# Sheet1.net
KiCad netlist of a schematic drawn in Altium Designer
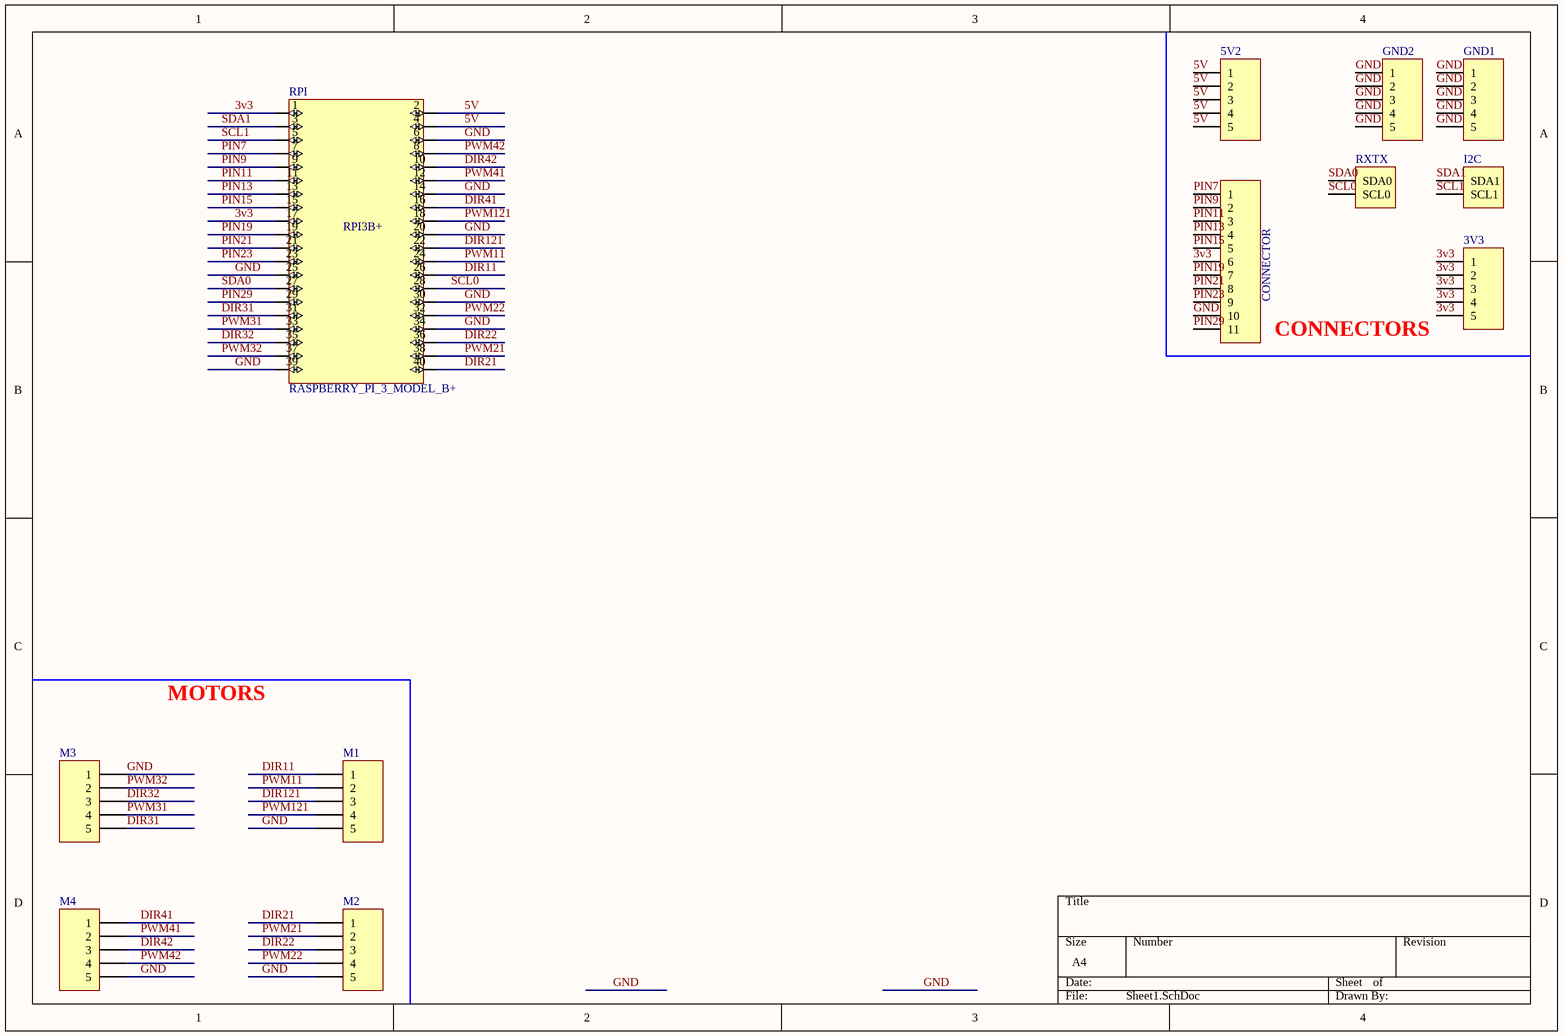
[diagram p0: Sheet1.SchDoc]

(export (version "E")
  (design (tool "Eeschema 10.0.6"))
  (components
    (comp (ref "3V3")
      (value "Header 5")
      (footprint "HDR1X5")
      (description "Header, 5-Pin")
      (fields (field (name "PUBLISHER") "Altium Limited"))
      (libsource (lib "Miscellaneous Connectors") (part "Header 5"))
    )
    (comp (ref "5V2")
      (value "Header 5")
      (footprint "HDR1X5")
      (description "Header, 5-Pin")
      (fields (field (name "PUBLISHER") "Altium Limited"))
      (libsource (lib "Miscellaneous Connectors") (part "Header 5"))
    )
    (comp (ref "CONNECTOR")
      (value "Header 11")
      (footprint "HDR1X11")
      (description "Header, 11-Pin")
      (fields (field (name "PUBLISHER") "Altium Limited"))
      (libsource (lib "Miscellaneous Connectors") (part "Header 11"))
    )
    (comp (ref "GND1")
      (value "Header 5")
      (footprint "HDR1X5")
      (description "Header, 5-Pin")
      (fields (field (name "PUBLISHER") "Altium Limited"))
      (libsource (lib "Miscellaneous Connectors") (part "Header 5"))
    )
    (comp (ref "GND2")
      (value "Header 5")
      (footprint "HDR1X5")
      (description "Header, 5-Pin")
      (fields (field (name "PUBLISHER") "Altium Limited"))
      (libsource (lib "Miscellaneous Connectors") (part "Header 5"))
    )
    (comp (ref "I2C")
      (value "Header 2")
      (footprint "HDR1X2")
      (description "Header, 2-Pin")
      (fields (field (name "PUBLISHER") "Altium Limited"))
      (libsource (lib "Miscellaneous Connectors") (part "Header 2"))
    )
    (comp (ref "M1")
      (value "Header 5")
      (footprint "HDR1X5")
      (description "Header, 5-Pin")
      (fields (field (name "PUBLISHER") "Altium Limited"))
      (libsource (lib "Miscellaneous Connectors") (part "Header 5"))
    )
    (comp (ref "M2")
      (value "Header 5")
      (footprint "HDR1X5")
      (description "Header, 5-Pin")
      (fields (field (name "PUBLISHER") "Altium Limited"))
      (libsource (lib "Miscellaneous Connectors") (part "Header 5"))
    )
    (comp (ref "M3")
      (value "Header 5")
      (footprint "HDR1X5")
      (description "Header, 5-Pin")
      (fields (field (name "PUBLISHER") "Altium Limited"))
      (libsource (lib "") (part "Header 5_1"))
    )
    (comp (ref "M4")
      (value "Header 5")
      (footprint "HDR1X5")
      (description "Header, 5-Pin")
      (fields (field (name "PUBLISHER") "Altium Limited"))
      (libsource (lib "") (part "Header 5_1"))
    )
    (comp (ref "RPI")
      (value "RASPBERRY_PI_3_MODEL_B+")
      (footprint "MODULE_RASPBERRY_PI_3_MODEL_B+")
      (fields (field (name "MF") "Raspberry Pi") (field (name "MP") "RASPBERRY PI 3 MODEL B+"))
      (libsource (lib "RASPBERRY_PI_3_MODEL_B+") (part "RASPBERRY_PI_3_MODEL_B+"))
    )
    (comp (ref "RXTX")
      (value "Header 2")
      (footprint "HDR1X2")
      (description "Header, 2-Pin")
      (fields (field (name "PUBLISHER") "Altium Limited"))
      (libsource (lib "Miscellaneous Connectors") (part "Header 2"))
    )
  )
  (nets
    (net (code "1") (name "/3v3") (class "Default")
      (node (ref "3V3") (pin "1") (pinfunction "1_1") (pintype "passive"))
      (node (ref "3V3") (pin "2") (pinfunction "2_2") (pintype "passive"))
      (node (ref "3V3") (pin "3") (pinfunction "3_3") (pintype "passive"))
      (node (ref "3V3") (pin "4") (pinfunction "4_4") (pintype "passive"))
      (node (ref "3V3") (pin "5") (pinfunction "5_5") (pintype "passive"))
      (node (ref "CONNECTOR") (pin "6") (pinfunction "6_6") (pintype "passive"))
      (node (ref "RPI") (pin "1") (pinfunction "1_1") (pintype "bidirectional"))
      (node (ref "RPI") (pin "17") (pinfunction "17_17") (pintype "bidirectional"))
    )
    (net (code "2") (name "/5V") (class "Default")
      (node (ref "5V2") (pin "1") (pinfunction "1_1") (pintype "passive"))
      (node (ref "5V2") (pin "2") (pinfunction "2_2") (pintype "passive"))
      (node (ref "5V2") (pin "3") (pinfunction "3_3") (pintype "passive"))
      (node (ref "5V2") (pin "4") (pinfunction "4_4") (pintype "passive"))
      (node (ref "5V2") (pin "5") (pinfunction "5_5") (pintype "passive"))
      (node (ref "RPI") (pin "2") (pinfunction "2_2") (pintype "bidirectional"))
      (node (ref "RPI") (pin "4") (pinfunction "4_4") (pintype "bidirectional"))
    )
    (net (code "3") (name "/DIR11") (class "Default")
      (node (ref "M1") (pin "1") (pinfunction "1_1") (pintype "passive"))
      (node (ref "RPI") (pin "26") (pinfunction "26_26") (pintype "bidirectional"))
    )
    (net (code "4") (name "/DIR21") (class "Default")
      (node (ref "M2") (pin "1") (pinfunction "1_1") (pintype "passive"))
      (node (ref "RPI") (pin "40") (pinfunction "40_40") (pintype "bidirectional"))
    )
    (net (code "5") (name "/DIR22") (class "Default")
      (node (ref "M2") (pin "3") (pinfunction "3_3") (pintype "passive"))
      (node (ref "RPI") (pin "36") (pinfunction "36_36") (pintype "bidirectional"))
    )
    (net (code "6") (name "/DIR31") (class "Default")
      (node (ref "M3") (pin "5") (pinfunction "5_5") (pintype "passive"))
      (node (ref "RPI") (pin "31") (pinfunction "31_31") (pintype "bidirectional"))
    )
    (net (code "7") (name "/DIR32") (class "Default")
      (node (ref "M3") (pin "3") (pinfunction "3_3") (pintype "passive"))
      (node (ref "RPI") (pin "35") (pinfunction "35_35") (pintype "bidirectional"))
    )
    (net (code "8") (name "/DIR41") (class "Default")
      (node (ref "M4") (pin "1") (pinfunction "1_1") (pintype "passive"))
      (node (ref "RPI") (pin "16") (pinfunction "16_16") (pintype "bidirectional"))
    )
    (net (code "9") (name "/DIR42") (class "Default")
      (node (ref "M4") (pin "3") (pinfunction "3_3") (pintype "passive"))
      (node (ref "RPI") (pin "10") (pinfunction "10_10") (pintype "bidirectional"))
    )
    (net (code "10") (name "/DIR121") (class "Default")
      (node (ref "M1") (pin "3") (pinfunction "3_3") (pintype "passive"))
      (node (ref "RPI") (pin "22") (pinfunction "22_22") (pintype "bidirectional"))
    )
    (net (code "11") (name "/GND") (class "Default")
      (node (ref "CONNECTOR") (pin "10") (pinfunction "10_10") (pintype "passive"))
      (node (ref "GND1") (pin "1") (pinfunction "1_1") (pintype "passive"))
      (node (ref "GND1") (pin "2") (pinfunction "2_2") (pintype "passive"))
      (node (ref "GND1") (pin "3") (pinfunction "3_3") (pintype "passive"))
      (node (ref "GND1") (pin "4") (pinfunction "4_4") (pintype "passive"))
      (node (ref "GND1") (pin "5") (pinfunction "5_5") (pintype "passive"))
      (node (ref "GND2") (pin "1") (pinfunction "1_1") (pintype "passive"))
      (node (ref "GND2") (pin "2") (pinfunction "2_2") (pintype "passive"))
      (node (ref "GND2") (pin "3") (pinfunction "3_3") (pintype "passive"))
      (node (ref "GND2") (pin "4") (pinfunction "4_4") (pintype "passive"))
      (node (ref "GND2") (pin "5") (pinfunction "5_5") (pintype "passive"))
      (node (ref "M1") (pin "5") (pinfunction "5_5") (pintype "passive"))
      (node (ref "M2") (pin "5") (pinfunction "5_5") (pintype "passive"))
      (node (ref "M3") (pin "1") (pinfunction "1_1") (pintype "passive"))
      (node (ref "M4") (pin "5") (pinfunction "5_5") (pintype "passive"))
      (node (ref "RPI") (pin "14") (pinfunction "14_14") (pintype "bidirectional"))
      (node (ref "RPI") (pin "20") (pinfunction "20_20") (pintype "bidirectional"))
      (node (ref "RPI") (pin "25") (pinfunction "25_25") (pintype "bidirectional"))
      (node (ref "RPI") (pin "30") (pinfunction "30_30") (pintype "bidirectional"))
      (node (ref "RPI") (pin "34") (pinfunction "34_34") (pintype "bidirectional"))
      (node (ref "RPI") (pin "39") (pinfunction "39_39") (pintype "bidirectional"))
      (node (ref "RPI") (pin "6") (pinfunction "6_6") (pintype "bidirectional"))
    )
    (net (code "12") (name "/PIN7") (class "Default")
      (node (ref "CONNECTOR") (pin "1") (pinfunction "1_1") (pintype "passive"))
      (node (ref "RPI") (pin "7") (pinfunction "7_7") (pintype "bidirectional"))
    )
    (net (code "13") (name "/PIN9") (class "Default")
      (node (ref "CONNECTOR") (pin "2") (pinfunction "2_2") (pintype "passive"))
      (node (ref "RPI") (pin "9") (pinfunction "9_9") (pintype "bidirectional"))
    )
    (net (code "14") (name "/PIN11") (class "Default")
      (node (ref "CONNECTOR") (pin "3") (pinfunction "3_3") (pintype "passive"))
      (node (ref "RPI") (pin "11") (pinfunction "11_11") (pintype "bidirectional"))
    )
    (net (code "15") (name "/PIN13") (class "Default")
      (node (ref "CONNECTOR") (pin "4") (pinfunction "4_4") (pintype "passive"))
      (node (ref "RPI") (pin "13") (pinfunction "13_13") (pintype "bidirectional"))
    )
    (net (code "16") (name "/PIN15") (class "Default")
      (node (ref "CONNECTOR") (pin "5") (pinfunction "5_5") (pintype "passive"))
      (node (ref "RPI") (pin "15") (pinfunction "15_15") (pintype "bidirectional"))
    )
    (net (code "17") (name "/PIN19") (class "Default")
      (node (ref "CONNECTOR") (pin "7") (pinfunction "7_7") (pintype "passive"))
      (node (ref "RPI") (pin "19") (pinfunction "19_19") (pintype "bidirectional"))
    )
    (net (code "18") (name "/PIN21") (class "Default")
      (node (ref "CONNECTOR") (pin "8") (pinfunction "8_8") (pintype "passive"))
      (node (ref "RPI") (pin "21") (pinfunction "21_21") (pintype "bidirectional"))
    )
    (net (code "19") (name "/PIN23") (class "Default")
      (node (ref "CONNECTOR") (pin "9") (pinfunction "9_9") (pintype "passive"))
      (node (ref "RPI") (pin "23") (pinfunction "23_23") (pintype "bidirectional"))
    )
    (net (code "20") (name "/PIN29") (class "Default")
      (node (ref "CONNECTOR") (pin "11") (pinfunction "11_11") (pintype "passive"))
      (node (ref "RPI") (pin "29") (pinfunction "29_29") (pintype "bidirectional"))
    )
    (net (code "21") (name "/PWM11") (class "Default")
      (node (ref "M1") (pin "2") (pinfunction "2_2") (pintype "passive"))
      (node (ref "RPI") (pin "24") (pinfunction "24_24") (pintype "bidirectional"))
    )
    (net (code "22") (name "/PWM21") (class "Default")
      (node (ref "M2") (pin "2") (pinfunction "2_2") (pintype "passive"))
      (node (ref "RPI") (pin "38") (pinfunction "38_38") (pintype "bidirectional"))
    )
    (net (code "23") (name "/PWM22") (class "Default")
      (node (ref "M2") (pin "4") (pinfunction "4_4") (pintype "passive"))
      (node (ref "RPI") (pin "32") (pinfunction "32_32") (pintype "bidirectional"))
    )
    (net (code "24") (name "/PWM31") (class "Default")
      (node (ref "M3") (pin "4") (pinfunction "4_4") (pintype "passive"))
      (node (ref "RPI") (pin "33") (pinfunction "33_33") (pintype "bidirectional"))
    )
    (net (code "25") (name "/PWM32") (class "Default")
      (node (ref "M3") (pin "2") (pinfunction "2_2") (pintype "passive"))
      (node (ref "RPI") (pin "37") (pinfunction "37_37") (pintype "bidirectional"))
    )
    (net (code "26") (name "/PWM41") (class "Default")
      (node (ref "M4") (pin "2") (pinfunction "2_2") (pintype "passive"))
      (node (ref "RPI") (pin "12") (pinfunction "12_12") (pintype "bidirectional"))
    )
    (net (code "27") (name "/PWM42") (class "Default")
      (node (ref "M4") (pin "4") (pinfunction "4_4") (pintype "passive"))
      (node (ref "RPI") (pin "8") (pinfunction "8_8") (pintype "bidirectional"))
    )
    (net (code "28") (name "/PWM121") (class "Default")
      (node (ref "M1") (pin "4") (pinfunction "4_4") (pintype "passive"))
      (node (ref "RPI") (pin "18") (pinfunction "18_18") (pintype "bidirectional"))
    )
    (net (code "29") (name "/SCL0") (class "Default")
      (node (ref "RPI") (pin "28") (pinfunction "28_28") (pintype "bidirectional"))
      (node (ref "RXTX") (pin "2") (pinfunction "SCL0_2") (pintype "passive"))
    )
    (net (code "30") (name "/SCL1") (class "Default")
      (node (ref "I2C") (pin "2") (pinfunction "SCL0_2") (pintype "passive"))
      (node (ref "RPI") (pin "5") (pinfunction "5_5") (pintype "bidirectional"))
    )
    (net (code "31") (name "/SDA0") (class "Default")
      (node (ref "RPI") (pin "27") (pinfunction "27_27") (pintype "bidirectional"))
      (node (ref "RXTX") (pin "1") (pinfunction "SDA0_1") (pintype "passive"))
    )
    (net (code "32") (name "/SDA1") (class "Default")
      (node (ref "I2C") (pin "1") (pinfunction "SDA0_1") (pintype "passive"))
      (node (ref "RPI") (pin "3") (pinfunction "3_3") (pintype "bidirectional"))
    )
  )
)
